# ESC_A.net
KiCad netlist of a schematic drawn in Altium Designer
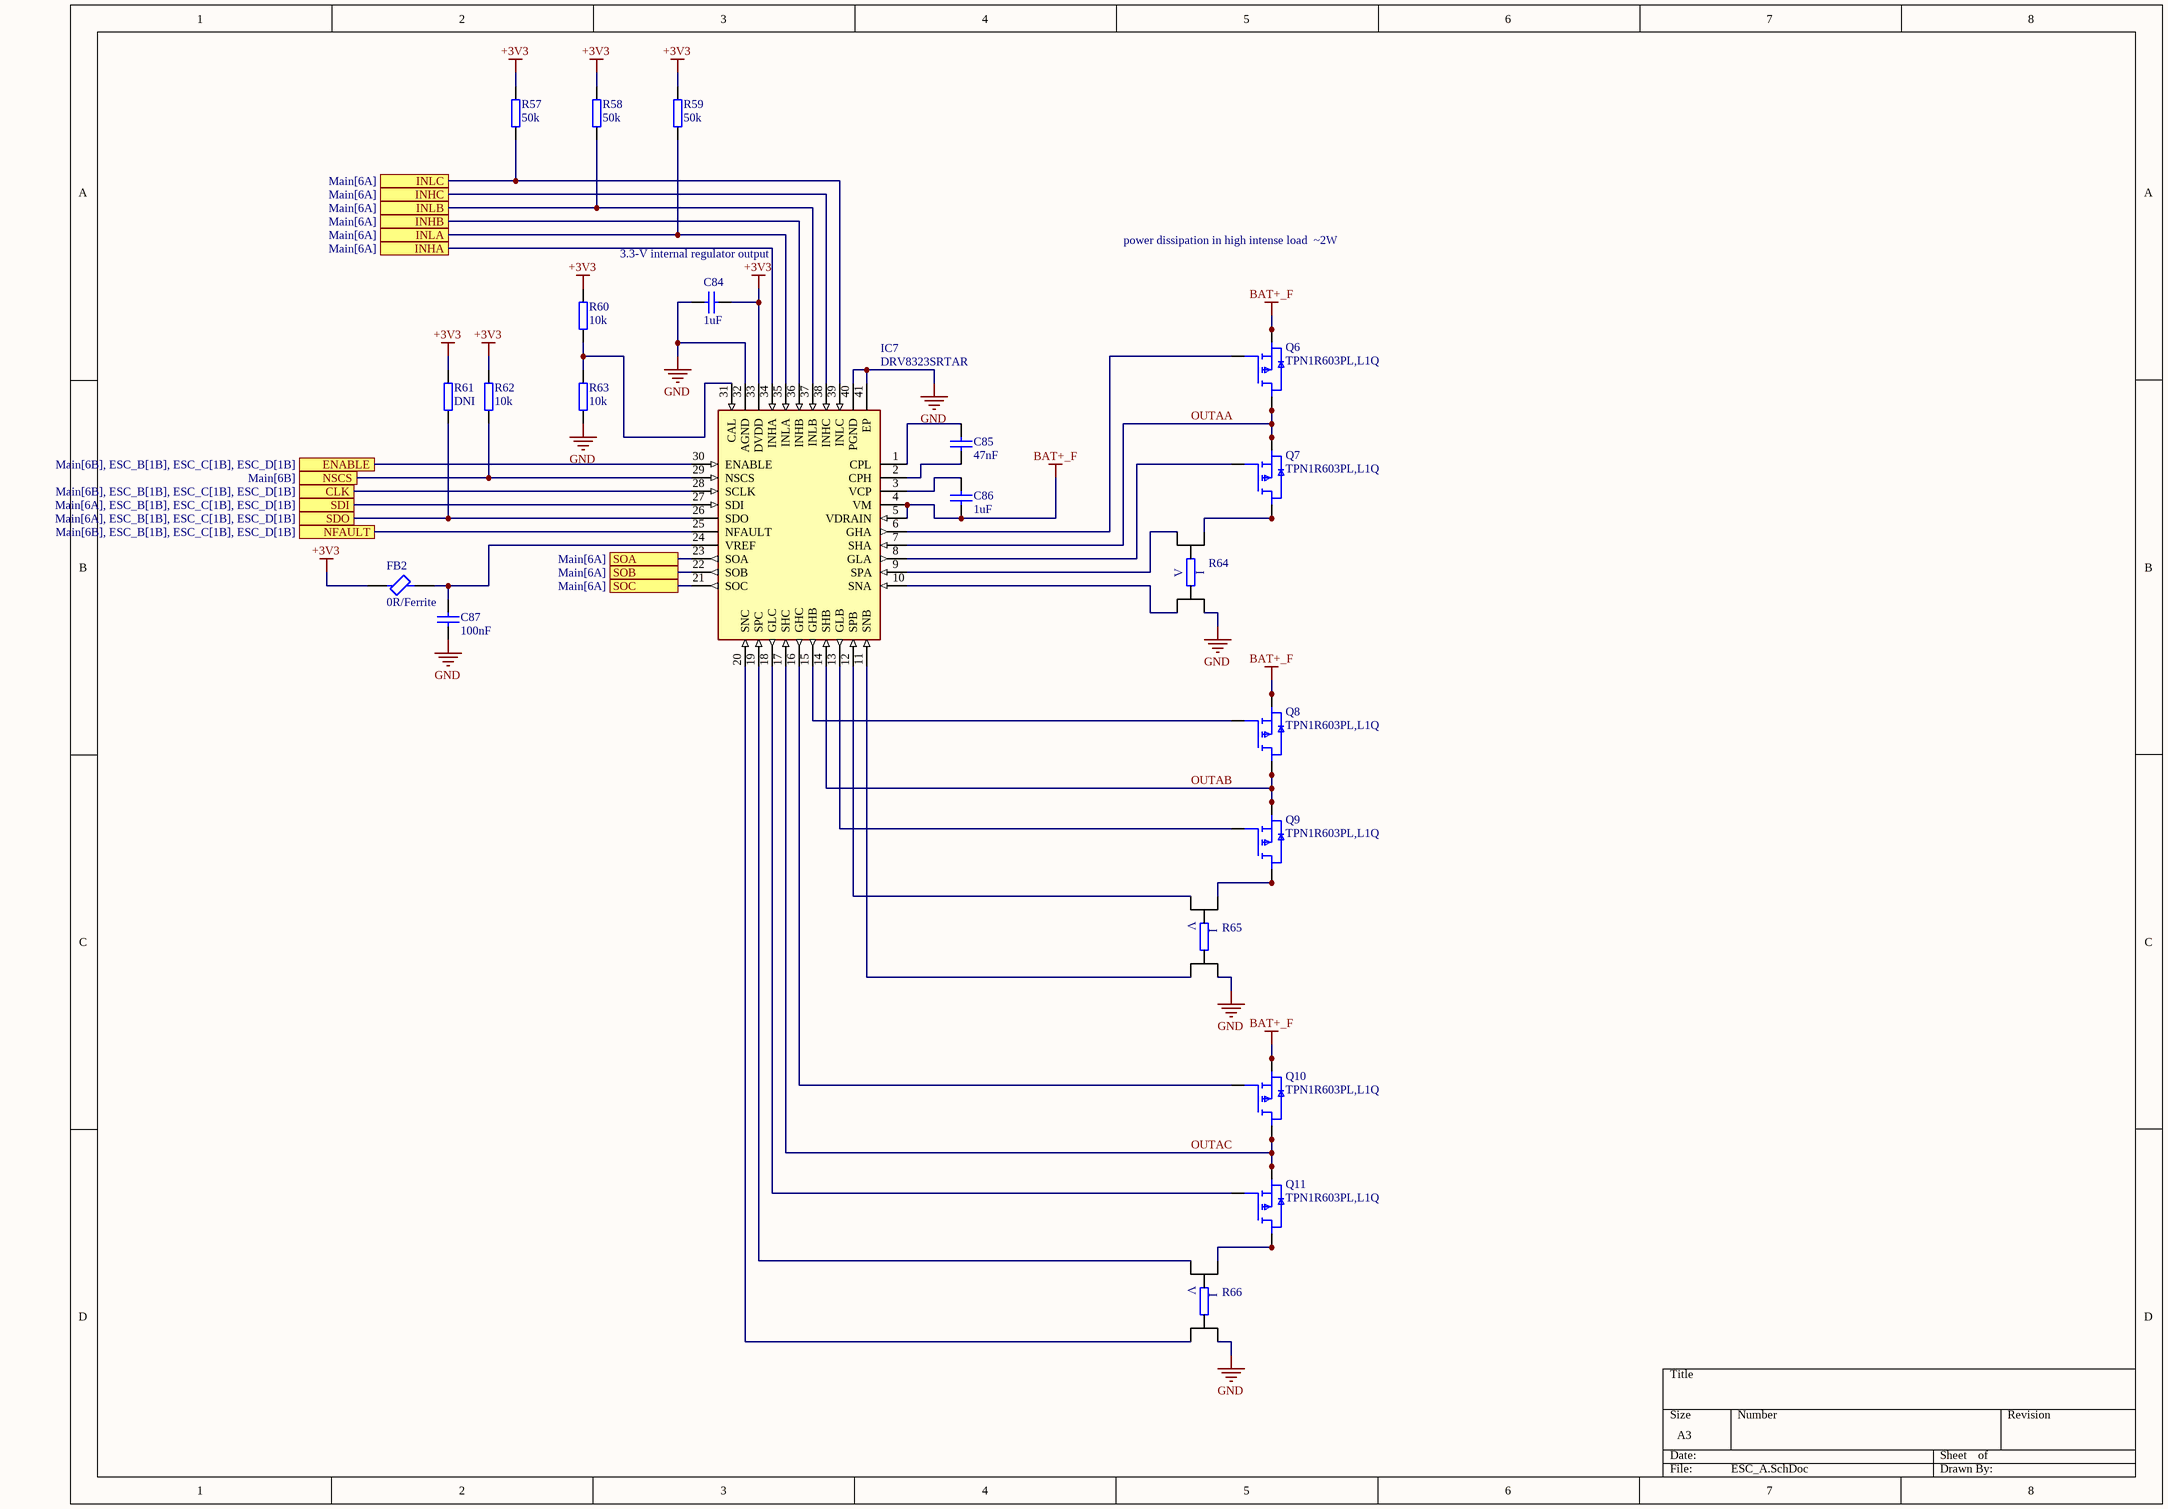
[diagram p0: ESC_A.SchDoc]

(export (version "E")
  (design (tool "Eeschema 10.0.6"))
  (components
    (comp (ref "C84")
      (value "1uF")
      (footprint "CAP0402")
      (fields
        (field (name "VOLTAGE") "50V")
        (field (name "MANUFACTURER_PART_NUMBER") "GRM155R61H105KE05J")
        (field (name "Comment") "Cap0402")
      )
      (libsource (lib "capacitorsSMD") (part "Cap0402"))
    )
    (comp (ref "C85")
      (value "47nF")
      (footprint "CAP0603")
      (description "50V")
      (fields (field (name "Comment") "Cap0603") (field (name "PUBLISHER") "Altium Limited"))
      (libsource (lib "capacitorsSMD") (part "CapSMD0603"))
    )
    (comp (ref "C86")
      (value "1uF")
      (footprint "CAP0603")
      (description "50V")
      (fields (field (name "Comment") "Cap0603") (field (name "PUBLISHER") "Altium Limited"))
      (libsource (lib "capacitorsSMD") (part "CapSMD0603"))
    )
    (comp (ref "C87")
      (value "100nF")
      (footprint "CAP0402")
      (fields
        (field (name "VOLTAGE") "50V")
        (field (name "MANUFACTURER_PART_NUMBER") "GRM155R71H104ME14D")
        (field (name "Comment") "Cap0402")
      )
      (libsource (lib "capacitorsSMD") (part "Cap0402"))
    )
    (comp (ref "FB2")
      (value "0R/Ferrite")
      (footprint "SamacSys:NFZ15SG152SN10B")
      (description "Ferrite Bead")
      (fields
        (field (name "MANUFACTURER_PART_NUMBER") "BLM15PE471SH1D")
        (field (name "MOUSER PART NUMBER") "81-BLM15PE471SH1D")
      )
      (libsource (lib "SamacSys") (part "BLM15PE471SH1D"))
    )
    (comp (ref "IC7")
      (value "DRV8323SRTAR")
      (footprint "SamacSys:QFN50P600X600X80-41N-D")
      (description "Integrated Circuit")
      (fields (field (name "MOUSER PART NUMBER") "595-DRV8323SRTAR"))
      (libsource (lib "*") (part "DRV8323SRTAR"))
    )
    (comp (ref "Q6")
      (value "TPN1R603PL,L1Q")
      (footprint "SamacSys:TPN1R603PLL1Q")
      (description "MOSFET (N-Channel)")
      (fields (field (name "MOUSER PART NUMBER") "757-TPN1R603PLL1Q"))
      (libsource (lib "SamacSys") (part "TPN1R603PL,L1Q"))
    )
    (comp (ref "Q7")
      (value "TPN1R603PL,L1Q")
      (footprint "SamacSys:TPN1R603PLL1Q")
      (description "MOSFET (N-Channel)")
      (fields (field (name "MOUSER PART NUMBER") "757-TPN1R603PLL1Q"))
      (libsource (lib "SamacSys") (part "TPN1R603PL,L1Q"))
    )
    (comp (ref "Q8")
      (value "TPN1R603PL,L1Q")
      (footprint "SamacSys:TPN1R603PLL1Q")
      (description "MOSFET (N-Channel)")
      (fields (field (name "MOUSER PART NUMBER") "757-TPN1R603PLL1Q"))
      (libsource (lib "SamacSys") (part "TPN1R603PL,L1Q"))
    )
    (comp (ref "Q9")
      (value "TPN1R603PL,L1Q")
      (footprint "SamacSys:TPN1R603PLL1Q")
      (description "MOSFET (N-Channel)")
      (fields (field (name "MOUSER PART NUMBER") "757-TPN1R603PLL1Q"))
      (libsource (lib "SamacSys") (part "TPN1R603PL,L1Q"))
    )
    (comp (ref "Q10")
      (value "TPN1R603PL,L1Q")
      (footprint "SamacSys:TPN1R603PLL1Q")
      (description "MOSFET (N-Channel)")
      (fields (field (name "MOUSER PART NUMBER") "757-TPN1R603PLL1Q"))
      (libsource (lib "SamacSys") (part "TPN1R603PL,L1Q"))
    )
    (comp (ref "Q11")
      (value "TPN1R603PL,L1Q")
      (footprint "SamacSys:TPN1R603PLL1Q")
      (description "MOSFET (N-Channel)")
      (fields (field (name "MOUSER PART NUMBER") "757-TPN1R603PLL1Q"))
      (libsource (lib "SamacSys") (part "TPN1R603PL,L1Q"))
    )
    (comp (ref "R57")
      (value "50k")
      (footprint "RES0402")
      (fields (field (name "MANUFACTURER_PART_NUMBER") "TNPW040249K9DEED") (field (name "Comment") "Res0402"))
      (libsource (lib "resistorSMD") (part "Res0402"))
    )
    (comp (ref "R58")
      (value "50k")
      (footprint "RES0402")
      (fields (field (name "MANUFACTURER_PART_NUMBER") "TNPW040249K9DEED") (field (name "Comment") "Res0402"))
      (libsource (lib "resistorSMD") (part "Res0402"))
    )
    (comp (ref "R59")
      (value "50k")
      (footprint "RES0402")
      (fields (field (name "MANUFACTURER_PART_NUMBER") "TNPW040249K9DEED") (field (name "Comment") "Res0402"))
      (libsource (lib "resistorSMD") (part "Res0402"))
    )
    (comp (ref "R60")
      (value "10k")
      (footprint "RES0402")
      (fields (field (name "MANUFACTURER_PART_NUMBER") "ERA-2AED103X") (field (name "Comment") "Res0402"))
      (libsource (lib "resistorSMD") (part "Res0402"))
    )
    (comp (ref "R61")
      (value "DNI")
      (footprint "RES0402")
      (fields (field (name "Comment") "Res0402"))
      (libsource (lib "resistorSMD") (part "Res0402"))
    )
    (comp (ref "R62")
      (value "10k")
      (footprint "RES0402")
      (fields (field (name "MANUFACTURER_PART_NUMBER") "ERA-2AED103X") (field (name "Comment") "Res0402"))
      (libsource (lib "resistorSMD") (part "Res0402"))
    )
    (comp (ref "R63")
      (value "10k")
      (footprint "RES0402")
      (fields (field (name "MANUFACTURER_PART_NUMBER") "ERA-2AED103X") (field (name "Comment") "Res0402"))
      (libsource (lib "resistorSMD") (part "Res0402"))
    )
    (comp (ref "R64")
      (value "WSK12161L000FEA")
      (footprint "SamacSys:WSK12161L000FEA")
      (description "Resistor")
      (fields
        (field (name "MANUFACTURER_PART_NUMBER") "WSK1216L5000FEA")
        (field (name "MOUSER PART NUMBER") "71-WSK1216L5000FEA")
      )
      (libsource (lib "SamacSys") (part "WSK1216L5000FEA"))
    )
    (comp (ref "R65")
      (value "WSK12161L000FEA")
      (footprint "SamacSys:WSK12161L000FEA")
      (description "Resistor")
      (fields
        (field (name "MANUFACTURER_PART_NUMBER") "WSK1216L5000FEA")
        (field (name "MOUSER PART NUMBER") "71-WSK1216L5000FEA")
      )
      (libsource (lib "SamacSys") (part "WSK1216L5000FEA"))
    )
    (comp (ref "R66")
      (value "WSK12161L000FEA")
      (footprint "SamacSys:WSK12161L000FEA")
      (description "Resistor")
      (fields
        (field (name "MANUFACTURER_PART_NUMBER") "WSK1216L5000FEA")
        (field (name "MOUSER PART NUMBER") "71-WSK1216L5000FEA")
      )
      (libsource (lib "SamacSys") (part "WSK1216L5000FEA"))
    )
  )
  (nets
    (net (code "1") (name "+3V3") (class "Default")
      (node (ref "C84") (pin "2") (pinfunction "2_2") (pintype "passive"))
      (node (ref "FB2") (pin "1") (pinfunction "1_1") (pintype "passive"))
      (node (ref "IC7") (pin "33") (pinfunction "DVDD_33") (pintype "power_in"))
      (node (ref "R57") (pin "2") (pinfunction "2_2") (pintype "passive"))
      (node (ref "R58") (pin "2") (pinfunction "2_2") (pintype "passive"))
      (node (ref "R59") (pin "2") (pinfunction "2_2") (pintype "passive"))
      (node (ref "R60") (pin "2") (pinfunction "2_2") (pintype "passive"))
      (node (ref "R61") (pin "2") (pinfunction "2_2") (pintype "passive"))
      (node (ref "R62") (pin "2") (pinfunction "2_2") (pintype "passive"))
    )
    (net (code "2") (name "/CLK") (class "Default")
      (node (ref "IC7") (pin "28") (pinfunction "SCLK_28") (pintype "input"))
    )
    (net (code "3") (name "/ENABLE") (class "Default")
      (node (ref "IC7") (pin "30") (pinfunction "ENABLE_30") (pintype "input"))
    )
    (net (code "4") (name "/INHA") (class "Default")
      (node (ref "IC7") (pin "34") (pinfunction "INHA_34") (pintype "input"))
    )
    (net (code "5") (name "/INHB") (class "Default")
      (node (ref "IC7") (pin "36") (pinfunction "INHB_36") (pintype "input"))
    )
    (net (code "6") (name "/INHC") (class "Default")
      (node (ref "IC7") (pin "38") (pinfunction "INHC_38") (pintype "input"))
    )
    (net (code "7") (name "/INLA") (class "Default")
      (node (ref "IC7") (pin "35") (pinfunction "INLA_35") (pintype "input"))
      (node (ref "R59") (pin "1") (pinfunction "1_1") (pintype "passive"))
    )
    (net (code "8") (name "/INLB") (class "Default")
      (node (ref "IC7") (pin "37") (pinfunction "INLB_37") (pintype "input"))
      (node (ref "R58") (pin "1") (pinfunction "1_1") (pintype "passive"))
    )
    (net (code "9") (name "/INLC") (class "Default")
      (node (ref "IC7") (pin "39") (pinfunction "INLC_39") (pintype "input"))
      (node (ref "R57") (pin "1") (pinfunction "1_1") (pintype "passive"))
    )
    (net (code "10") (name "/NFAULT") (class "Default")
      (node (ref "IC7") (pin "25") (pinfunction "NFAULT_25") (pintype "passive"))
    )
    (net (code "11") (name "/NSCS") (class "Default")
      (node (ref "IC7") (pin "29") (pinfunction "NSCS_29") (pintype "input"))
      (node (ref "R62") (pin "1") (pinfunction "1_1") (pintype "passive"))
    )
    (net (code "12") (name "/OUTAA") (class "Default")
      (node (ref "IC7") (pin "7") (pinfunction "SHA_7") (pintype "input"))
      (node (ref "Q6") (pin "5") (pinfunction "D_1_5") (pintype "passive"))
      (node (ref "Q6") (pin "6") (pinfunction "D_2_6") (pintype "passive"))
      (node (ref "Q6") (pin "7") (pinfunction "D_3_7") (pintype "passive"))
      (node (ref "Q6") (pin "8") (pinfunction "D_4_8") (pintype "passive"))
      (node (ref "Q6") (pin "9") (pinfunction "D_4_9") (pintype "passive"))
      (node (ref "Q7") (pin "1") (pinfunction "S_1_1") (pintype "passive"))
      (node (ref "Q7") (pin "2") (pinfunction "S_2_2") (pintype "passive"))
      (node (ref "Q7") (pin "3") (pinfunction "S_3_3") (pintype "passive"))
    )
    (net (code "13") (name "/OUTAB") (class "Default")
      (node (ref "IC7") (pin "14") (pinfunction "SHB_14") (pintype "input"))
      (node (ref "Q8") (pin "5") (pinfunction "D_1_5") (pintype "passive"))
      (node (ref "Q8") (pin "6") (pinfunction "D_2_6") (pintype "passive"))
      (node (ref "Q8") (pin "7") (pinfunction "D_3_7") (pintype "passive"))
      (node (ref "Q8") (pin "8") (pinfunction "D_4_8") (pintype "passive"))
      (node (ref "Q8") (pin "9") (pinfunction "D_4_9") (pintype "passive"))
      (node (ref "Q9") (pin "1") (pinfunction "S_1_1") (pintype "passive"))
      (node (ref "Q9") (pin "2") (pinfunction "S_2_2") (pintype "passive"))
      (node (ref "Q9") (pin "3") (pinfunction "S_3_3") (pintype "passive"))
    )
    (net (code "14") (name "/OUTAC") (class "Default")
      (node (ref "IC7") (pin "17") (pinfunction "SHC_17") (pintype "input"))
      (node (ref "Q10") (pin "5") (pinfunction "D_1_5") (pintype "passive"))
      (node (ref "Q10") (pin "6") (pinfunction "D_2_6") (pintype "passive"))
      (node (ref "Q10") (pin "7") (pinfunction "D_3_7") (pintype "passive"))
      (node (ref "Q10") (pin "8") (pinfunction "D_4_8") (pintype "passive"))
      (node (ref "Q10") (pin "9") (pinfunction "D_4_9") (pintype "passive"))
      (node (ref "Q11") (pin "1") (pinfunction "S_1_1") (pintype "passive"))
      (node (ref "Q11") (pin "2") (pinfunction "S_2_2") (pintype "passive"))
      (node (ref "Q11") (pin "3") (pinfunction "S_3_3") (pintype "passive"))
    )
    (net (code "15") (name "/SDI") (class "Default")
      (node (ref "IC7") (pin "27") (pinfunction "SDI_27") (pintype "input"))
    )
    (net (code "16") (name "/SDO") (class "Default")
      (node (ref "IC7") (pin "26") (pinfunction "SDO_26") (pintype "passive"))
      (node (ref "R61") (pin "1") (pinfunction "1_1") (pintype "passive"))
    )
    (net (code "17") (name "/SOA") (class "Default")
      (node (ref "IC7") (pin "23") (pinfunction "SOA_23") (pintype "output"))
    )
    (net (code "18") (name "/SOB") (class "Default")
      (node (ref "IC7") (pin "22") (pinfunction "SOB_22") (pintype "output"))
    )
    (net (code "19") (name "/SOC") (class "Default")
      (node (ref "IC7") (pin "21") (pinfunction "SOC_21") (pintype "output"))
    )
    (net (code "20") (name "BAT+_F") (class "Default")
      (node (ref "C86") (pin "1") (pinfunction "1_1") (pintype "passive"))
      (node (ref "IC7") (pin "4") (pinfunction "VM_4") (pintype "power_in"))
      (node (ref "IC7") (pin "5") (pinfunction "VDRAIN_5") (pintype "input"))
      (node (ref "Q10") (pin "1") (pinfunction "S_1_1") (pintype "passive"))
      (node (ref "Q10") (pin "2") (pinfunction "S_2_2") (pintype "passive"))
      (node (ref "Q10") (pin "3") (pinfunction "S_3_3") (pintype "passive"))
      (node (ref "Q6") (pin "1") (pinfunction "S_1_1") (pintype "passive"))
      (node (ref "Q6") (pin "2") (pinfunction "S_2_2") (pintype "passive"))
      (node (ref "Q6") (pin "3") (pinfunction "S_3_3") (pintype "passive"))
      (node (ref "Q8") (pin "1") (pinfunction "S_1_1") (pintype "passive"))
      (node (ref "Q8") (pin "2") (pinfunction "S_2_2") (pintype "passive"))
      (node (ref "Q8") (pin "3") (pinfunction "S_3_3") (pintype "passive"))
    )
    (net (code "21") (name "GND") (class "Default")
      (node (ref "C84") (pin "1") (pinfunction "1_1") (pintype "passive"))
      (node (ref "C87") (pin "1") (pinfunction "1_1") (pintype "passive"))
      (node (ref "IC7") (pin "32") (pinfunction "AGND_32") (pintype "power_in"))
      (node (ref "IC7") (pin "40") (pinfunction "PGND_40") (pintype "power_in"))
      (node (ref "IC7") (pin "41") (pinfunction "EP_41") (pintype "power_in"))
      (node (ref "R63") (pin "1") (pinfunction "1_1") (pintype "passive"))
      (node (ref "R64") (pin "1") (pinfunction "1_1") (pintype "passive"))
      (node (ref "R65") (pin "4") (pinfunction "4_4") (pintype "passive"))
      (node (ref "R66") (pin "4") (pinfunction "4_4") (pintype "passive"))
    )
    (net (code "22") (name "Net-(IC7-CAL)") (class "Default")
      (node (ref "IC7") (pin "31") (pinfunction "CAL_31") (pintype "input"))
      (node (ref "R60") (pin "1") (pinfunction "1_1") (pintype "passive"))
      (node (ref "R63") (pin "2") (pinfunction "2_2") (pintype "passive"))
    )
    (net (code "23") (name "Net-(IC7-CPH)") (class "Default")
      (node (ref "C85") (pin "1") (pinfunction "1_1") (pintype "passive"))
      (node (ref "IC7") (pin "2") (pinfunction "CPH_2") (pintype "power_in"))
    )
    (net (code "24") (name "Net-(IC7-CPL)") (class "Default")
      (node (ref "C85") (pin "2") (pinfunction "2_2") (pintype "passive"))
      (node (ref "IC7") (pin "1") (pinfunction "CPL_1") (pintype "power_in"))
    )
    (net (code "25") (name "Net-(IC7-GHA)") (class "Default")
      (node (ref "IC7") (pin "6") (pinfunction "GHA_6") (pintype "output"))
      (node (ref "Q6") (pin "4") (pinfunction "G_4") (pintype "passive"))
    )
    (net (code "26") (name "Net-(IC7-GHB)") (class "Default")
      (node (ref "IC7") (pin "15") (pinfunction "GHB_15") (pintype "output"))
      (node (ref "Q8") (pin "4") (pinfunction "G_4") (pintype "passive"))
    )
    (net (code "27") (name "Net-(IC7-GHC)") (class "Default")
      (node (ref "IC7") (pin "16") (pinfunction "GHC_16") (pintype "output"))
      (node (ref "Q10") (pin "4") (pinfunction "G_4") (pintype "passive"))
    )
    (net (code "28") (name "Net-(IC7-GLA)") (class "Default")
      (node (ref "IC7") (pin "8") (pinfunction "GLA_8") (pintype "output"))
      (node (ref "Q7") (pin "4") (pinfunction "G_4") (pintype "passive"))
    )
    (net (code "29") (name "Net-(IC7-GLB)") (class "Default")
      (node (ref "IC7") (pin "13") (pinfunction "GLB_13") (pintype "output"))
      (node (ref "Q9") (pin "4") (pinfunction "G_4") (pintype "passive"))
    )
    (net (code "30") (name "Net-(IC7-GLC)") (class "Default")
      (node (ref "IC7") (pin "18") (pinfunction "GLC_18") (pintype "output"))
      (node (ref "Q11") (pin "4") (pinfunction "G_4") (pintype "passive"))
    )
    (net (code "31") (name "Net-(IC7-SNA)") (class "Default")
      (node (ref "IC7") (pin "10") (pinfunction "SNA_10") (pintype "input"))
      (node (ref "R64") (pin "2") (pinfunction "2_2") (pintype "passive"))
    )
    (net (code "32") (name "Net-(IC7-SNB)") (class "Default")
      (node (ref "IC7") (pin "11") (pinfunction "SNB_11") (pintype "input"))
      (node (ref "R65") (pin "3") (pinfunction "3_3") (pintype "passive"))
    )
    (net (code "33") (name "Net-(IC7-SNC)") (class "Default")
      (node (ref "IC7") (pin "20") (pinfunction "SNC_20") (pintype "input"))
      (node (ref "R66") (pin "3") (pinfunction "3_3") (pintype "passive"))
    )
    (net (code "34") (name "Net-(IC7-SPA)") (class "Default")
      (node (ref "IC7") (pin "9") (pinfunction "SPA_9") (pintype "input"))
      (node (ref "R64") (pin "3") (pinfunction "3_3") (pintype "passive"))
    )
    (net (code "35") (name "Net-(IC7-SPB)") (class "Default")
      (node (ref "IC7") (pin "12") (pinfunction "SPB_12") (pintype "input"))
      (node (ref "R65") (pin "2") (pinfunction "2_2") (pintype "passive"))
    )
    (net (code "36") (name "Net-(IC7-SPC)") (class "Default")
      (node (ref "IC7") (pin "19") (pinfunction "SPC_19") (pintype "input"))
      (node (ref "R66") (pin "2") (pinfunction "2_2") (pintype "passive"))
    )
    (net (code "37") (name "Net-(IC7-VCP)") (class "Default")
      (node (ref "C86") (pin "2") (pinfunction "2_2") (pintype "passive"))
      (node (ref "IC7") (pin "3") (pinfunction "VCP_3") (pintype "power_in"))
    )
    (net (code "38") (name "Net-(IC7-VREF)") (class "Default")
      (node (ref "C87") (pin "2") (pinfunction "2_2") (pintype "passive"))
      (node (ref "FB2") (pin "2") (pinfunction "2_2") (pintype "passive"))
      (node (ref "IC7") (pin "24") (pinfunction "VREF_24") (pintype "power_in"))
    )
    (net (code "39") (name "Net-(Q7-D_1)") (class "Default")
      (node (ref "Q7") (pin "5") (pinfunction "D_1_5") (pintype "passive"))
      (node (ref "Q7") (pin "6") (pinfunction "D_2_6") (pintype "passive"))
      (node (ref "Q7") (pin "7") (pinfunction "D_3_7") (pintype "passive"))
      (node (ref "Q7") (pin "8") (pinfunction "D_4_8") (pintype "passive"))
      (node (ref "Q7") (pin "9") (pinfunction "D_4_9") (pintype "passive"))
      (node (ref "R64") (pin "4") (pinfunction "4_4") (pintype "passive"))
    )
    (net (code "40") (name "Net-(Q9-D_1)") (class "Default")
      (node (ref "Q9") (pin "5") (pinfunction "D_1_5") (pintype "passive"))
      (node (ref "Q9") (pin "6") (pinfunction "D_2_6") (pintype "passive"))
      (node (ref "Q9") (pin "7") (pinfunction "D_3_7") (pintype "passive"))
      (node (ref "Q9") (pin "8") (pinfunction "D_4_8") (pintype "passive"))
      (node (ref "Q9") (pin "9") (pinfunction "D_4_9") (pintype "passive"))
      (node (ref "R65") (pin "1") (pinfunction "1_1") (pintype "passive"))
    )
    (net (code "41") (name "Net-(Q11-D_1)") (class "Default")
      (node (ref "Q11") (pin "5") (pinfunction "D_1_5") (pintype "passive"))
      (node (ref "Q11") (pin "6") (pinfunction "D_2_6") (pintype "passive"))
      (node (ref "Q11") (pin "7") (pinfunction "D_3_7") (pintype "passive"))
      (node (ref "Q11") (pin "8") (pinfunction "D_4_8") (pintype "passive"))
      (node (ref "Q11") (pin "9") (pinfunction "D_4_9") (pintype "passive"))
      (node (ref "R66") (pin "1") (pinfunction "1_1") (pintype "passive"))
    )
  )
)
